# zmena_polarity_BDD_2.net
KiCad netlist of a schematic drawn in Altium Designer
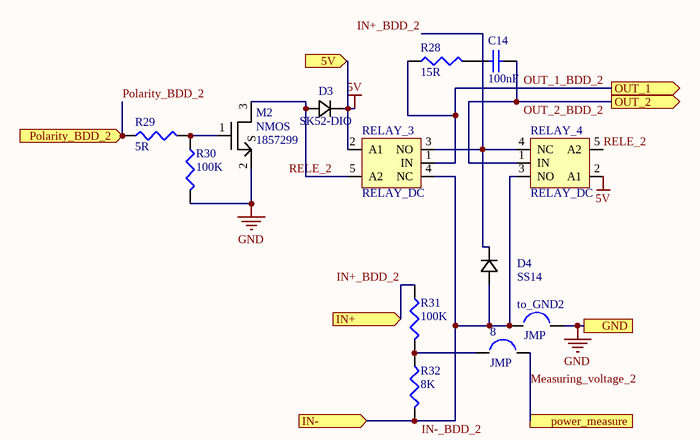
[diagram p0: zmena polarity_BDD_2.SchDoc]

(export (version "E")
  (design (tool "Eeschema 10.0.6"))
  (components
    (comp (ref "8") (value "JMP") (footprint "JMP") (libsource (lib "SamacSys") (part "JMP")))
    (comp (ref "C14")
      (value "100nF")
      (footprint "1608[0603]")
      (description "Capacitor (Semiconductor SIM Model)")
      (fields (field (name "PUBLISHER") "Altium Limited"))
      (libsource (lib "Miscellaneous Devices") (part "Cap Semi"))
    )
    (comp (ref "D3")
      (value "SK52-DIO")
      (footprint "D5A20V")
      (libsource (lib "SCH_Aquatec") (part "D_5A_20V"))
    )
    (comp (ref "D4") (value "SS14") (footprint "D5A20V") (libsource (lib "SCH_Aquatec") (part "D_5A_20V")))
    (comp (ref "M2")
      (value "NMOS")
      (footprint "SOT23")
      (fields (field (name "SUPPLIER PART NUMBER 1") "1857299"))
      (libsource (lib "SchematicLib_JP") (part "NMOS"))
    )
    (comp (ref "R28")
      (value "15R")
      (footprint "J1-0603")
      (description "Resistor")
      (fields (field (name "PUBLISHER") "Altium Limited"))
      (libsource (lib "Miscellaneous Devices") (part "Res3"))
    )
    (comp (ref "R29")
      (value "5R")
      (footprint "J1-0603")
      (description "Resistor")
      (fields (field (name "PUBLISHER") "Altium Limited"))
      (libsource (lib "Miscellaneous Devices") (part "Res3"))
    )
    (comp (ref "R30")
      (value "100K")
      (footprint "J1-0603")
      (description "Resistor")
      (fields (field (name "PUBLISHER") "Altium Limited"))
      (libsource (lib "Miscellaneous Devices") (part "Res3"))
    )
    (comp (ref "R31")
      (value "100K")
      (footprint "J1-0603")
      (description "Resistor")
      (fields (field (name "PUBLISHER") "Altium Limited"))
      (libsource (lib "Miscellaneous Devices") (part "Res3"))
    )
    (comp (ref "R32")
      (value "8K")
      (footprint "J1-0603")
      (description "Resistor")
      (fields (field (name "PUBLISHER") "Altium Limited"))
      (libsource (lib "Miscellaneous Devices") (part "Res3"))
    )
    (comp (ref "RELAY_3")
      (value "RELAY_DC")
      (footprint "RELAY_DC")
      (description "RM51-3011-85-1005")
      (libsource (lib "") (part "RELAY_DC_1"))
    )
    (comp (ref "RELAY_4")
      (value "RELAY_DC")
      (footprint "RELAY_DC")
      (description "RM51-3011-85-1005")
      (libsource (lib "SCH_Aquatec") (part "RELAY_DC"))
    )
    (comp (ref "to_GND2") (value "JMP") (footprint "JMP") (libsource (lib "SamacSys") (part "JMP")))
  )
  (nets
    (net (code "1") (name "/IN+_BDD_2") (class "Default")
      (node (ref "D4") (pin "1") (pinfunction "1_1") (pintype "passive"))
      (node (ref "R31") (pin "1") (pinfunction "1_1") (pintype "passive"))
      (node (ref "RELAY_3") (pin "3") (pinfunction "NO_3") (pintype "passive"))
      (node (ref "RELAY_4") (pin "4") (pinfunction "NC_4") (pintype "passive"))
    )
    (net (code "2") (name "/IN-_BDD_2") (class "Default")
      (node (ref "D4") (pin "2") (pinfunction "2_2") (pintype "passive"))
      (node (ref "R32") (pin "2") (pinfunction "2_2") (pintype "passive"))
      (node (ref "RELAY_3") (pin "4") (pinfunction "NC_4") (pintype "passive"))
      (node (ref "RELAY_4") (pin "3") (pinfunction "NO_3") (pintype "passive"))
      (node (ref "to_GND2") (pin "1") (pinfunction "1_1") (pintype "passive"))
    )
    (net (code "3") (name "/Measuring_voltage_2") (class "Default")
      (node (ref "8") (pin "2") (pinfunction "2_2") (pintype "passive"))
    )
    (net (code "4") (name "/OUT_1_BDD_2") (class "Default")
      (node (ref "R28") (pin "1") (pinfunction "1_1") (pintype "passive"))
      (node (ref "RELAY_3") (pin "1") (pinfunction "IN_1") (pintype "passive"))
    )
    (net (code "5") (name "/OUT_2_BDD_2") (class "Default")
      (node (ref "C14") (pin "2") (pinfunction "2_2") (pintype "passive"))
      (node (ref "RELAY_4") (pin "1") (pinfunction "IN_1") (pintype "passive"))
    )
    (net (code "6") (name "/Polarity_BDD_2") (class "Default")
      (node (ref "R29") (pin "1") (pinfunction "1_1") (pintype "passive"))
    )
    (net (code "7") (name "/RELE_2") (class "Default")
      (node (ref "D3") (pin "2") (pinfunction "2_2") (pintype "passive"))
      (node (ref "M2") (pin "3") (pinfunction "D_3") (pintype "passive"))
      (node (ref "RELAY_3") (pin "5") (pinfunction "A2_5") (pintype "passive"))
      (node (ref "RELAY_4") (pin "5") (pinfunction "A2_5") (pintype "passive"))
    )
    (net (code "8") (name "5V") (class "Default")
      (node (ref "D3") (pin "1") (pinfunction "1_1") (pintype "passive"))
      (node (ref "RELAY_3") (pin "2") (pinfunction "A1_2") (pintype "passive"))
      (node (ref "RELAY_4") (pin "2") (pinfunction "A1_2") (pintype "passive"))
    )
    (net (code "9") (name "GND") (class "Default")
      (node (ref "M2") (pin "2") (pinfunction "S_2") (pintype "passive"))
      (node (ref "R30") (pin "2") (pinfunction "2_2") (pintype "passive"))
      (node (ref "to_GND2") (pin "2") (pinfunction "2_2") (pintype "passive"))
    )
    (net (code "10") (name "Net-(8-Pad1)") (class "Default")
      (node (ref "8") (pin "1") (pinfunction "1_1") (pintype "passive"))
      (node (ref "R31") (pin "2") (pinfunction "2_2") (pintype "passive"))
      (node (ref "R32") (pin "1") (pinfunction "1_1") (pintype "passive"))
    )
    (net (code "11") (name "Net-(C14-Pad1)") (class "Default")
      (node (ref "C14") (pin "1") (pinfunction "1_1") (pintype "passive"))
      (node (ref "R28") (pin "2") (pinfunction "2_2") (pintype "passive"))
    )
    (net (code "12") (name "Net-(M2-G)") (class "Default")
      (node (ref "M2") (pin "1") (pinfunction "G_1") (pintype "passive"))
      (node (ref "R29") (pin "2") (pinfunction "2_2") (pintype "passive"))
      (node (ref "R30") (pin "1") (pinfunction "1_1") (pintype "passive"))
    )
  )
)
